# J-ST-Link.net
KiCad netlist of a schematic drawn in EAGLE
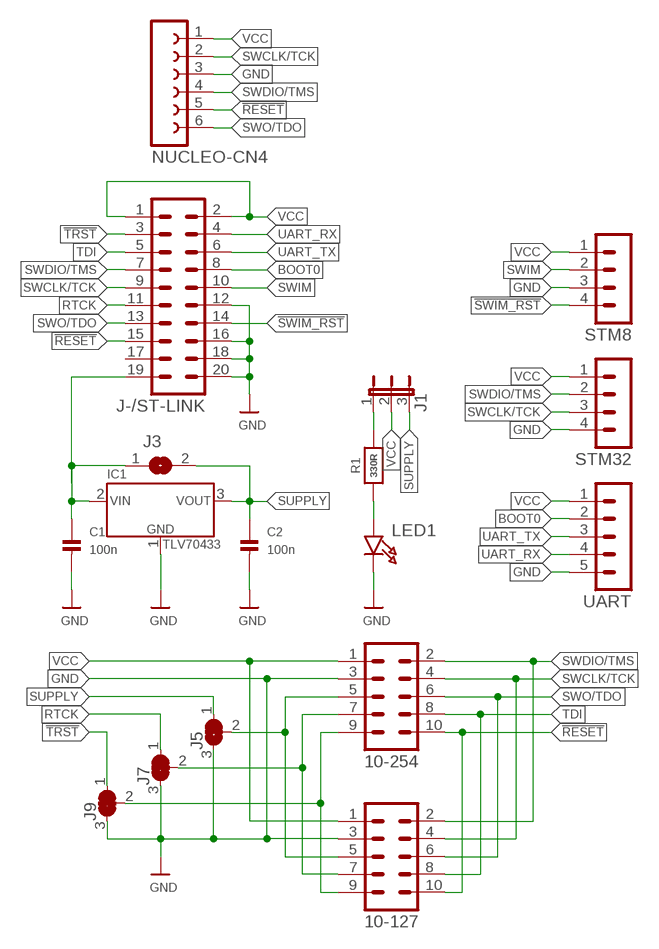
[diagram p0: schematic, sheet 1]

(export (version "E")
  (design (tool "Eeschema 10.0.6"))
  (components
    (comp (ref "10-127")
      (value "CON-HARTING-ML_ML10S")
      (footprint "eagle-import:CON-HARTING-ML_ML10S")
      (libsource (lib "eagle-import") (part "CON-HARTING-ML_ML10S"))
    )
    (comp (ref "10-254")
      (value "ML10")
      (footprint "eagle-import:ML10")
      (libsource (lib "eagle-import") (part "ML10"))
    )
    (comp (ref "C1")
      (value "100n")
      (footprint "eagle-import:_0603MP")
      (libsource (lib "eagle-import") (part "CAP_CERAMIC_0603MP"))
    )
    (comp (ref "C2")
      (value "100n")
      (footprint "eagle-import:_0603MP")
      (libsource (lib "eagle-import") (part "CAP_CERAMIC_0603MP"))
    )
    (comp (ref "IC1")
      (value "TLV70433")
      (footprint "eagle-import:SOT23-5")
      (libsource (lib "eagle-import") (part "TLV704XX"))
    )
    (comp (ref "J-/ST-LINK")
      (value "ML20")
      (footprint "eagle-import:ML20")
      (libsource (lib "eagle-import") (part "ML20"))
    )
    (comp (ref "J1")
      (value "JUMPER3LONG")
      (footprint "eagle-import:JUMPER3_LONG")
      (libsource (lib "eagle-import") (part "JUMPER3LONG"))
    )
    (comp (ref "J3")
      (value "SOLDERJUMPERSMALL_NOPRINT")
      (footprint "eagle-import:SOLDERJUMPER_SMALL_NOPRINT")
      (libsource (lib "eagle-import") (part "SOLDERJUMPERSMALL_NOPRINT"))
    )
    (comp (ref "J5")
      (value "SOLDERJUMPER_2WAY_CLOSED")
      (footprint "eagle-import:SOLDERJUMPER_2WAY_CLOSED_0603")
      (libsource (lib "eagle-import") (part "SOLDERJUMPER_2WAY_CLOSED"))
    )
    (comp (ref "J7")
      (value "SOLDERJUMPER_2WAY_CLOSED")
      (footprint "eagle-import:SOLDERJUMPER_2WAY_CLOSED_0603")
      (libsource (lib "eagle-import") (part "SOLDERJUMPER_2WAY_CLOSED"))
    )
    (comp (ref "J9")
      (value "SOLDERJUMPER_2WAY_CLOSED")
      (footprint "eagle-import:SOLDERJUMPER_2WAY_CLOSED_0603")
      (libsource (lib "eagle-import") (part "SOLDERJUMPER_2WAY_CLOSED"))
    )
    (comp (ref "LED1")
      (value "LED0603_NOOUTLINE")
      (footprint "eagle-import:CHIPLED_0603_NOOUTLINE")
      (libsource (lib "eagle-import") (part "LED0603_NOOUTLINE"))
    )
    (comp (ref "NUCLEO-CN4")
      (value "FE06WSQUARE")
      (footprint "eagle-import:FE06W_SQUARE")
      (libsource (lib "eagle-import") (part "FE06WSQUARE"))
    )
    (comp (ref "R1")
      (value "330R")
      (footprint "eagle-import:0603-NO")
      (libsource (lib "eagle-import") (part "RESISTOR_0603_NOOUT"))
    )
    (comp (ref "STM8")
      (value "MA04-1")
      (footprint "eagle-import:MA04-1")
      (libsource (lib "eagle-import") (part "MA04-1"))
    )
    (comp (ref "STM32")
      (value "MA04-1")
      (footprint "eagle-import:MA04-1")
      (libsource (lib "eagle-import") (part "MA04-1"))
    )
    (comp (ref "UART")
      (value "MA05-1")
      (footprint "eagle-import:MA05-1")
      (libsource (lib "eagle-import") (part "MA05-1"))
    )
  )
  (nets
    (net (code "1") (name "/~{RESET}") (class "Default")
      (node (ref "10-127") (pin "10") (pinfunction "10_10") (pintype "passive"))
      (node (ref "10-254") (pin "10") (pinfunction "10_10") (pintype "passive"))
      (node (ref "J-/ST-LINK") (pin "15") (pinfunction "15_15") (pintype "passive"))
      (node (ref "NUCLEO-CN4") (pin "5") (pinfunction "5_5") (pintype "passive"))
    )
    (net (code "2") (name "/~{SWIM_RST}") (class "Default")
      (node (ref "J-/ST-LINK") (pin "14") (pinfunction "14_14") (pintype "passive"))
      (node (ref "STM8") (pin "4") (pinfunction "4_4") (pintype "passive"))
    )
    (net (code "3") (name "/~{TRST}") (class "Default")
      (node (ref "J-/ST-LINK") (pin "3") (pinfunction "3_3") (pintype "passive"))
      (node (ref "J9") (pin "1") (pinfunction "1_1") (pintype "passive"))
    )
    (net (code "4") (name "BOOT0") (class "Default")
      (node (ref "J-/ST-LINK") (pin "8") (pinfunction "8_8") (pintype "passive"))
      (node (ref "UART") (pin "2") (pinfunction "2_2") (pintype "passive"))
    )
    (net (code "5") (name "GND") (class "Default")
      (node (ref "10-127") (pin "3") (pinfunction "3_3") (pintype "passive"))
      (node (ref "10-254") (pin "3") (pinfunction "3_3") (pintype "passive"))
      (node (ref "C1") (pin "2") (pinfunction "P$2_2") (pintype "passive"))
      (node (ref "C2") (pin "2") (pinfunction "P$2_2") (pintype "passive"))
      (node (ref "IC1") (pin "1") (pinfunction "GND_1") (pintype "bidirectional"))
      (node (ref "J-/ST-LINK") (pin "12") (pinfunction "12_12") (pintype "passive"))
      (node (ref "J-/ST-LINK") (pin "16") (pinfunction "16_16") (pintype "passive"))
      (node (ref "J-/ST-LINK") (pin "18") (pinfunction "18_18") (pintype "passive"))
      (node (ref "J-/ST-LINK") (pin "20") (pinfunction "20_20") (pintype "passive"))
      (node (ref "J5") (pin "3") (pinfunction "3_3") (pintype "passive"))
      (node (ref "J7") (pin "3") (pinfunction "3_3") (pintype "passive"))
      (node (ref "J9") (pin "3") (pinfunction "3_3") (pintype "passive"))
      (node (ref "LED1") (pin "C") (pinfunction "C_C") (pintype "passive"))
      (node (ref "NUCLEO-CN4") (pin "3") (pinfunction "3_3") (pintype "passive"))
      (node (ref "STM32") (pin "4") (pinfunction "4_4") (pintype "passive"))
      (node (ref "STM8") (pin "3") (pinfunction "3_3") (pintype "passive"))
      (node (ref "UART") (pin "5") (pinfunction "5_5") (pintype "passive"))
    )
    (net (code "6") (name "Net-(10-127-Pad5)") (class "Default")
      (node (ref "10-127") (pin "5") (pinfunction "5_5") (pintype "passive"))
      (node (ref "10-254") (pin "5") (pinfunction "5_5") (pintype "passive"))
      (node (ref "J5") (pin "2") (pinfunction "2_2") (pintype "passive"))
    )
    (net (code "7") (name "Net-(10-127-Pad7)") (class "Default")
      (node (ref "10-127") (pin "7") (pinfunction "7_7") (pintype "passive"))
      (node (ref "10-254") (pin "7") (pinfunction "7_7") (pintype "passive"))
      (node (ref "J7") (pin "2") (pinfunction "2_2") (pintype "passive"))
    )
    (net (code "8") (name "Net-(10-127-Pad9)") (class "Default")
      (node (ref "10-127") (pin "9") (pinfunction "9_9") (pintype "passive"))
      (node (ref "10-254") (pin "9") (pinfunction "9_9") (pintype "passive"))
      (node (ref "J9") (pin "2") (pinfunction "2_2") (pintype "passive"))
    )
    (net (code "9") (name "Net-(C1-P$1)") (class "Default")
      (node (ref "C1") (pin "1") (pinfunction "P$1_1") (pintype "passive"))
      (node (ref "IC1") (pin "2") (pinfunction "IN_2") (pintype "bidirectional"))
      (node (ref "J-/ST-LINK") (pin "19") (pinfunction "19_19") (pintype "passive"))
      (node (ref "J3") (pin "1") (pinfunction "1_1") (pintype "passive"))
    )
    (net (code "10") (name "Net-(J1-Pad1)") (class "Default")
      (node (ref "J1") (pin "1") (pinfunction "1_1") (pintype "passive"))
      (node (ref "R1") (pin "2") (pinfunction "2_2") (pintype "passive"))
    )
    (net (code "11") (name "Net-(LED1-PadA)") (class "Default")
      (node (ref "LED1") (pin "A") (pinfunction "A_A") (pintype "passive"))
      (node (ref "R1") (pin "1") (pinfunction "1_1") (pintype "passive"))
    )
    (net (code "12") (name "RTCK") (class "Default")
      (node (ref "J-/ST-LINK") (pin "11") (pinfunction "11_11") (pintype "passive"))
      (node (ref "J7") (pin "1") (pinfunction "1_1") (pintype "passive"))
    )
    (net (code "13") (name "SUPPLY") (class "Default")
      (node (ref "C2") (pin "1") (pinfunction "P$1_1") (pintype "passive"))
      (node (ref "IC1") (pin "3") (pinfunction "OUT_3") (pintype "bidirectional"))
      (node (ref "J1") (pin "3") (pinfunction "3_3") (pintype "passive"))
      (node (ref "J3") (pin "2") (pinfunction "2_2") (pintype "passive"))
      (node (ref "J5") (pin "1") (pinfunction "1_1") (pintype "passive"))
    )
    (net (code "14") (name "SWCLK{slash}TCK") (class "Default")
      (node (ref "10-127") (pin "4") (pinfunction "4_4") (pintype "passive"))
      (node (ref "10-254") (pin "4") (pinfunction "4_4") (pintype "passive"))
      (node (ref "J-/ST-LINK") (pin "9") (pinfunction "9_9") (pintype "passive"))
      (node (ref "NUCLEO-CN4") (pin "2") (pinfunction "2_2") (pintype "passive"))
      (node (ref "STM32") (pin "3") (pinfunction "3_3") (pintype "passive"))
    )
    (net (code "15") (name "SWDIO{slash}TMS") (class "Default")
      (node (ref "10-127") (pin "2") (pinfunction "2_2") (pintype "passive"))
      (node (ref "10-254") (pin "2") (pinfunction "2_2") (pintype "passive"))
      (node (ref "J-/ST-LINK") (pin "7") (pinfunction "7_7") (pintype "passive"))
      (node (ref "NUCLEO-CN4") (pin "4") (pinfunction "4_4") (pintype "passive"))
      (node (ref "STM32") (pin "2") (pinfunction "2_2") (pintype "passive"))
    )
    (net (code "16") (name "SWIM") (class "Default")
      (node (ref "J-/ST-LINK") (pin "10") (pinfunction "10_10") (pintype "passive"))
      (node (ref "STM8") (pin "2") (pinfunction "2_2") (pintype "passive"))
    )
    (net (code "17") (name "SWO{slash}TDO") (class "Default")
      (node (ref "10-127") (pin "6") (pinfunction "6_6") (pintype "passive"))
      (node (ref "10-254") (pin "6") (pinfunction "6_6") (pintype "passive"))
      (node (ref "J-/ST-LINK") (pin "13") (pinfunction "13_13") (pintype "passive"))
      (node (ref "NUCLEO-CN4") (pin "6") (pinfunction "6_6") (pintype "passive"))
    )
    (net (code "18") (name "TDI") (class "Default")
      (node (ref "10-127") (pin "8") (pinfunction "8_8") (pintype "passive"))
      (node (ref "10-254") (pin "8") (pinfunction "8_8") (pintype "passive"))
      (node (ref "J-/ST-LINK") (pin "5") (pinfunction "5_5") (pintype "passive"))
    )
    (net (code "19") (name "UART_RX") (class "Default")
      (node (ref "J-/ST-LINK") (pin "4") (pinfunction "4_4") (pintype "passive"))
      (node (ref "UART") (pin "4") (pinfunction "4_4") (pintype "passive"))
    )
    (net (code "20") (name "UART_TX") (class "Default")
      (node (ref "J-/ST-LINK") (pin "6") (pinfunction "6_6") (pintype "passive"))
      (node (ref "UART") (pin "3") (pinfunction "3_3") (pintype "passive"))
    )
    (net (code "21") (name "VCC") (class "Default")
      (node (ref "10-127") (pin "1") (pinfunction "1_1") (pintype "passive"))
      (node (ref "10-254") (pin "1") (pinfunction "1_1") (pintype "passive"))
      (node (ref "J-/ST-LINK") (pin "1") (pinfunction "1_1") (pintype "passive"))
      (node (ref "J-/ST-LINK") (pin "2") (pinfunction "2_2") (pintype "passive"))
      (node (ref "J1") (pin "2") (pinfunction "2_2") (pintype "passive"))
      (node (ref "NUCLEO-CN4") (pin "1") (pinfunction "1_1") (pintype "passive"))
      (node (ref "STM32") (pin "1") (pinfunction "1_1") (pintype "passive"))
      (node (ref "STM8") (pin "1") (pinfunction "1_1") (pintype "passive"))
      (node (ref "UART") (pin "1") (pinfunction "1_1") (pintype "passive"))
    )
    (net (code "22") (name "unconnected-(J-/ST-LINK-Pad17)") (class "Default")
      (node (ref "J-/ST-LINK") (pin "17") (pinfunction "17_17") (pintype "passive"))
    )
  )
)
